# untitled.net
KiCad netlist of a schematic drawn in EAGLE
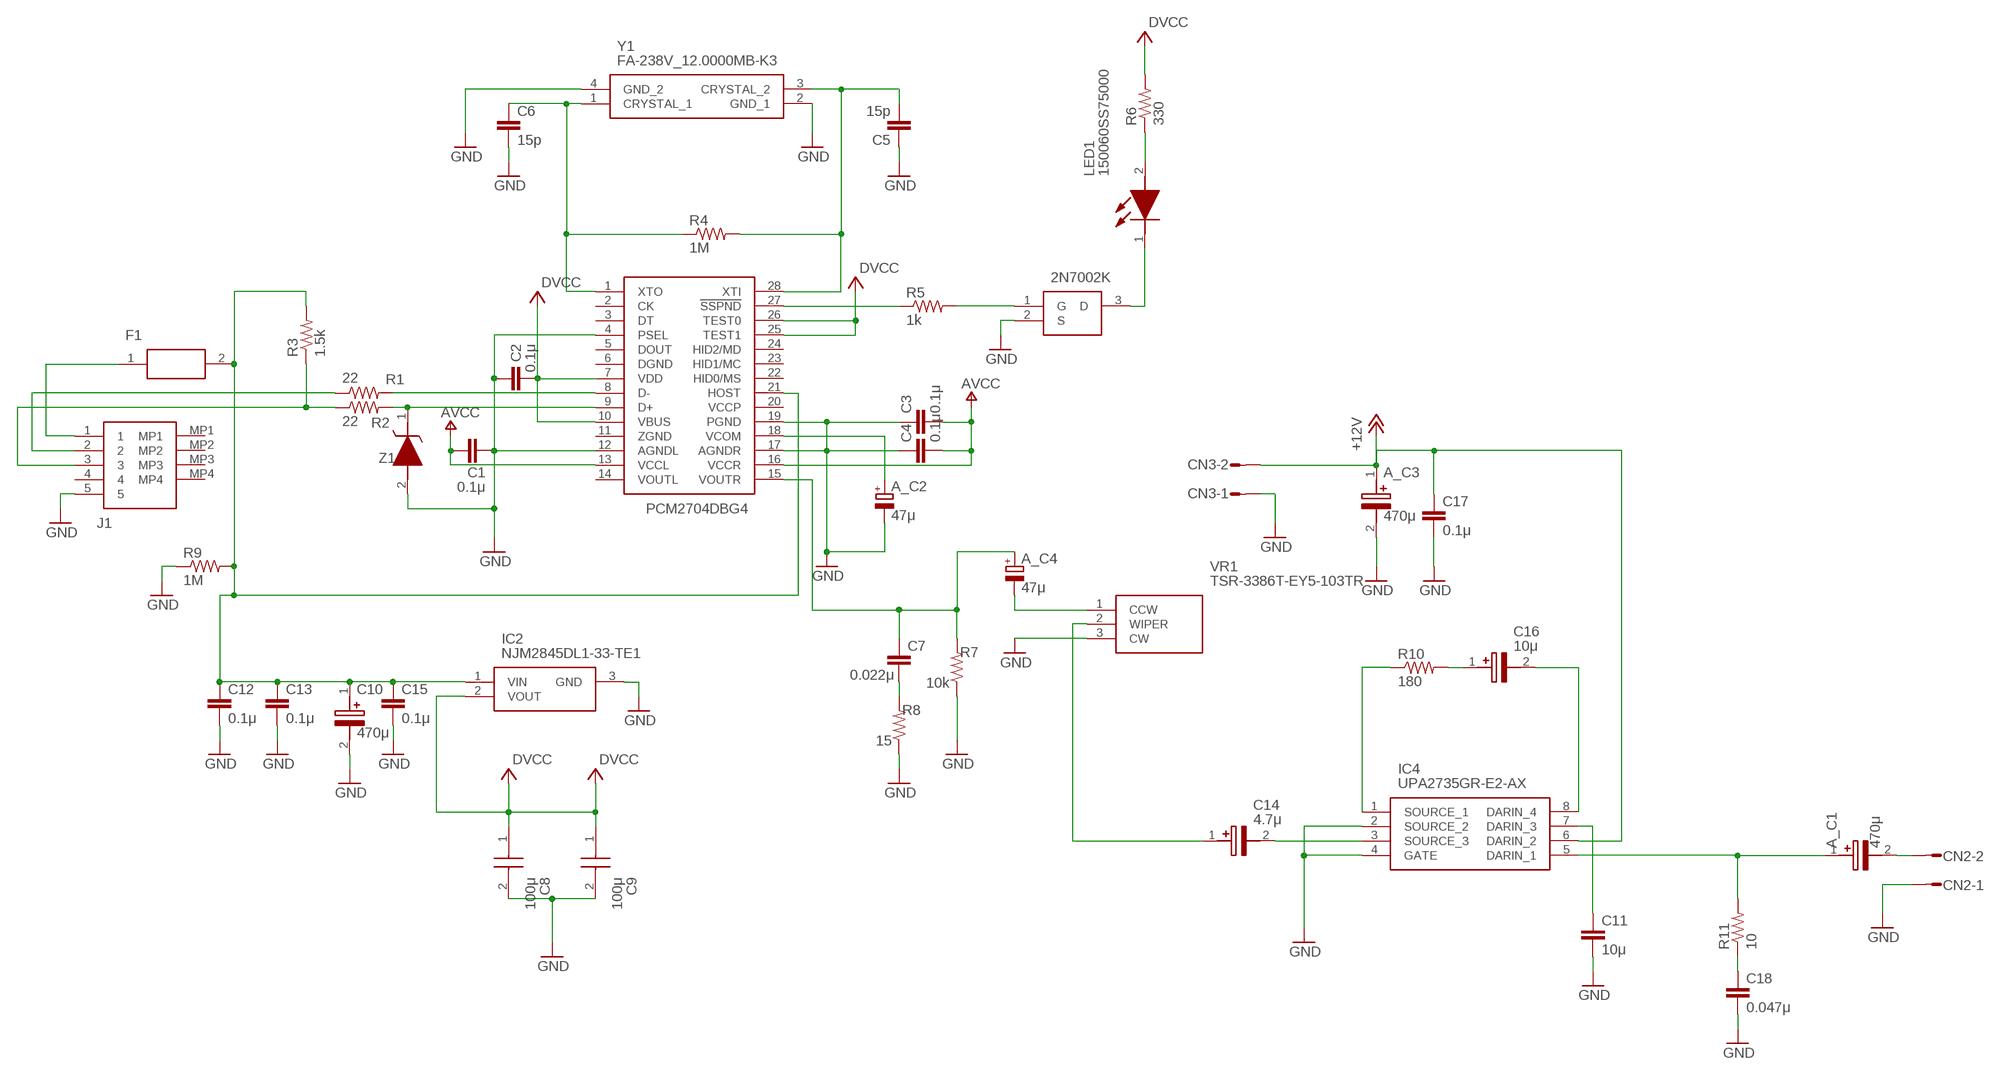
[diagram p0: schematic, sheet 1]

(export (version "E")
  (design (tool "Eeschema 10.0.6"))
  (components
    (comp (ref "A_C1")
      (value "470μ")
      (footprint "eagle-import:CAPPRD350W60D825H1150")
      (fields
        (field (name "MANUFACTURER_PART_NUMBER") "25PK470MEFC8X11.5")
        (field (name "MOUSER_PART_NUMBER") "232-25PK470MEFC8X115")
      )
      (libsource (lib "eagle-import") (part "25PK470MEFC8X11.5"))
    )
    (comp (ref "A_C2")
      (value "47μ")
      (footprint "eagle-import:UFG1E470MEM")
      (libsource (lib "eagle-import") (part "UFG1E470MEM"))
    )
    (comp (ref "A_C3")
      (value "470μ")
      (footprint "eagle-import:CAPPRD350W60D825H1150")
      (fields
        (field (name "MANUFACTURER_PART_NUMBER") "25PK470MEFC8X11.5")
        (field (name "MOUSER_PART_NUMBER") "232-25PK470MEFC8X115")
      )
      (libsource (lib "eagle-import") (part "25PK470MEFC8X11.5"))
    )
    (comp (ref "A_C4")
      (value "47μ")
      (footprint "eagle-import:UFG1E470MEM")
      (libsource (lib "eagle-import") (part "UFG1E470MEM"))
    )
    (comp (ref "C1")
      (value "0.1μ")
      (footprint "eagle-import:C0603")
      (libsource (lib "eagle-import") (part "C-EUC0603"))
    )
    (comp (ref "C2")
      (value "0.1μ")
      (footprint "eagle-import:C0603")
      (libsource (lib "eagle-import") (part "C-EUC0603"))
    )
    (comp (ref "C3")
      (value "0.1μ")
      (footprint "eagle-import:C0603")
      (libsource (lib "eagle-import") (part "C-EUC0603"))
    )
    (comp (ref "C4")
      (value "0.1μ")
      (footprint "eagle-import:C0603")
      (libsource (lib "eagle-import") (part "C-EUC0603"))
    )
    (comp (ref "C5")
      (value "15p")
      (footprint "eagle-import:C0603")
      (libsource (lib "eagle-import") (part "C-EUC0603"))
    )
    (comp (ref "C6")
      (value "15p")
      (footprint "eagle-import:C0603")
      (libsource (lib "eagle-import") (part "C-EUC0603"))
    )
    (comp (ref "C7")
      (value "0.022μ")
      (footprint "eagle-import:C0603")
      (libsource (lib "eagle-import") (part "C-EUC0603"))
    )
    (comp (ref "C8")
      (value "100μ")
      (footprint "eagle-import:PK(5X11)")
      (fields
        (field (name "MANUFACTURER_PART_NUMBER") "25PK100MEFC5X11")
        (field (name "MOUSER_PART_NUMBER") "232-25PK100MEFC5X11")
      )
      (libsource (lib "eagle-import") (part "25PK100MEFC5X11"))
    )
    (comp (ref "C9")
      (value "100μ")
      (footprint "eagle-import:PK(5X11)")
      (fields
        (field (name "MANUFACTURER_PART_NUMBER") "25PK100MEFC5X11")
        (field (name "MOUSER_PART_NUMBER") "232-25PK100MEFC5X11")
      )
      (libsource (lib "eagle-import") (part "25PK100MEFC5X11"))
    )
    (comp (ref "C10")
      (value "470μ")
      (footprint "eagle-import:CAPPRD350W60D825H1150")
      (fields
        (field (name "MANUFACTURER_PART_NUMBER") "25PK470MEFC8X11.5")
        (field (name "MOUSER_PART_NUMBER") "232-25PK470MEFC8X115")
      )
      (libsource (lib "eagle-import") (part "25PK470MEFC8X11.5"))
    )
    (comp (ref "C11")
      (value "10μ")
      (footprint "eagle-import:50F2D473J")
      (libsource (lib "eagle-import") (part "50F2D473J"))
    )
    (comp (ref "C12")
      (value "0.1μ")
      (footprint "eagle-import:C0603")
      (libsource (lib "eagle-import") (part "C-EUC0603"))
    )
    (comp (ref "C13")
      (value "0.1μ")
      (footprint "eagle-import:C0603")
      (libsource (lib "eagle-import") (part "C-EUC0603"))
    )
    (comp (ref "C14")
      (value "4.7μ")
      (footprint "eagle-import:CAPPRD200W50D525H1100")
      (fields (field (name "MANUFACTURER_PART_NUMBER") "50PK4R7MEFC5X11"))
      (libsource (lib "eagle-import") (part "50PK4R7MEFC5X11"))
    )
    (comp (ref "C15")
      (value "0.1μ")
      (footprint "eagle-import:C0603")
      (libsource (lib "eagle-import") (part "C-EUC0603"))
    )
    (comp (ref "C16")
      (value "10μ")
      (footprint "eagle-import:CAPPRD200W50D550H1250")
      (fields
        (field (name "MANUFACTURER_PART_NUMBER") "50PK10MEFC5X11")
        (field (name "MOUSER_PART_NUMBER") "232-50PK10MEFC5X11")
      )
      (libsource (lib "eagle-import") (part "50PK10MEFC5X11"))
    )
    (comp (ref "C17")
      (value "0.1μ")
      (footprint "eagle-import:C0603")
      (libsource (lib "eagle-import") (part "C-EUC0603"))
    )
    (comp (ref "C18")
      (value "0.047μ")
      (footprint "eagle-import:50F2D473J")
      (libsource (lib "eagle-import") (part "50F2D473J"))
    )
    (comp (ref "CN2")
      (value "S02P")
      (footprint "eagle-import:S02P")
      (libsource (lib "eagle-import") (part "S02P"))
    )
    (comp (ref "CN3")
      (value "S02P")
      (footprint "eagle-import:S02P")
      (libsource (lib "eagle-import") (part "S02P"))
    )
    (comp (ref "F1")
      (value "MICROSMD010-2")
      (footprint "eagle-import:MICROSMD175F2")
      (libsource (lib "eagle-import") (part "MICROSMD010-2"))
    )
    (comp (ref "IC1")
      (value "PCM2704DBG4")
      (footprint "eagle-import:SOP65P780X200-28N")
      (fields (field (name "MOUSER_PART_NUMBER") "595-PCM2704DBG4"))
      (libsource (lib "eagle-import") (part "PCM2704DBG4"))
    )
    (comp (ref "IC2")
      (value "NJM2845DL1-33-TE1")
      (footprint "eagle-import:TO-252-3-L1")
      (fields (field (name "MOUSER_PART_NUMBER") "513-NJM2845DL133-TE1"))
      (libsource (lib "eagle-import") (part "NJM2845DL1-33-TE1"))
    )
    (comp (ref "IC3")
      (value "2N7002K")
      (footprint "eagle-import:SOT65P210X110-3N")
      (fields
        (field (name "MANUFACTURER_PART_NUMBER") "2N7002KW")
        (field (name "MOUSER_PART_NUMBER") "512-2N7002KW")
      )
      (libsource (lib "eagle-import") (part "2N7002KW"))
    )
    (comp (ref "IC4")
      (value "UPA2735GR-E2-AX")
      (footprint "eagle-import:SOIC127P600X175-8N")
      (libsource (lib "eagle-import") (part "UPA2735GR-E2-AX"))
    )
    (comp (ref "J1")
      (value "USB2066-05-RBHM-15-STB-00-00-A")
      (footprint "eagle-import:USB206605RBHM15STB0000A")
      (fields (field (name "MOUSER_PART_NUMBER") "640-2665RBHM15STB00A"))
      (libsource (lib "eagle-import") (part "USB2066-05-RBHM-15-STB-00-00-A"))
    )
    (comp (ref "LED1")
      (value "150060SS75000")
      (footprint "eagle-import:LEDC1608X80N")
      (fields (field (name "MOUSER_PART_NUMBER") "710-150060SS75000"))
      (libsource (lib "eagle-import") (part "150060SS75000"))
    )
    (comp (ref "R1")
      (value "22")
      (footprint "eagle-import:R0603")
      (libsource (lib "eagle-import") (part "R-US_R0603"))
    )
    (comp (ref "R2")
      (value "22")
      (footprint "eagle-import:R0603")
      (libsource (lib "eagle-import") (part "R-US_R0603"))
    )
    (comp (ref "R3")
      (value "1.5k")
      (footprint "eagle-import:R0603")
      (libsource (lib "eagle-import") (part "R-US_R0603"))
    )
    (comp (ref "R4")
      (value "1M")
      (footprint "eagle-import:R0603")
      (libsource (lib "eagle-import") (part "R-US_R0603"))
    )
    (comp (ref "R5")
      (value "1k")
      (footprint "eagle-import:R0603")
      (libsource (lib "eagle-import") (part "R-US_R0603"))
    )
    (comp (ref "R6")
      (value "330")
      (footprint "eagle-import:R0603")
      (libsource (lib "eagle-import") (part "R-US_R0603"))
    )
    (comp (ref "R7")
      (value "10k")
      (footprint "eagle-import:R0603")
      (libsource (lib "eagle-import") (part "R-US_R0603"))
    )
    (comp (ref "R8")
      (value "15")
      (footprint "eagle-import:R0603")
      (libsource (lib "eagle-import") (part "R-US_R0603"))
    )
    (comp (ref "R9")
      (value "1M")
      (footprint "eagle-import:R0603")
      (libsource (lib "eagle-import") (part "R-US_R0603"))
    )
    (comp (ref "R10")
      (value "180")
      (footprint "eagle-import:R0603")
      (libsource (lib "eagle-import") (part "R-US_R0603"))
    )
    (comp (ref "R11")
      (value "10")
      (footprint "eagle-import:R0603")
      (libsource (lib "eagle-import") (part "R-US_R0603"))
    )
    (comp (ref "VR1")
      (value "TSR-3386T-EY5-103TR")
      (footprint "eagle-import:TSR3386TEY5103TR")
      (libsource (lib "eagle-import") (part "TSR-3386T-EY5-103TR"))
    )
    (comp (ref "Y1")
      (value "FA-238V_12.0000MB-K3")
      (footprint "eagle-import:FA238V120000MBK3")
      (fields
        (field (name "MANUFACTURER_PART_NUMBER") "FA-238V 12.0000MB-K3")
        (field (name "MOUSER_PART_NUMBER") "732-FA238V12.B-K3")
      )
      (libsource (lib "eagle-import") (part "FA-238V_12.0000MB-K3"))
    )
    (comp (ref "Z1")
      (value "UDZVTE-175.1B")
      (footprint "eagle-import:UDZVTE1751B")
      (fields (field (name "MOUSER_PART_NUMBER") "755-UDZVTE-175.1B"))
      (libsource (lib "eagle-import") (part "UDZVTE-175.1B"))
    )
  )
  (nets
    (net (code "1") (name "+12V") (class "Default")
      (node (ref "A_C3") (pin "1") (pinfunction "+_1") (pintype "bidirectional"))
      (node (ref "C17") (pin "1") (pinfunction "1_1") (pintype "passive"))
      (node (ref "CN3") (pin "2") (pinfunction "S_2") (pintype "passive"))
      (node (ref "IC4") (pin "6") (pinfunction "DARIN_2_6") (pintype "bidirectional"))
    )
    (net (code "2") (name "AVCC") (class "Default")
      (node (ref "C1") (pin "1") (pinfunction "1_1") (pintype "passive"))
      (node (ref "C3") (pin "2") (pinfunction "2_2") (pintype "passive"))
      (node (ref "C4") (pin "2") (pinfunction "2_2") (pintype "passive"))
      (node (ref "IC1") (pin "13") (pinfunction "VCCL_13") (pintype "bidirectional"))
      (node (ref "IC1") (pin "16") (pinfunction "VCCR_16") (pintype "bidirectional"))
    )
    (net (code "3") (name "DVCC") (class "Default")
      (node (ref "C2") (pin "2") (pinfunction "2_2") (pintype "passive"))
      (node (ref "C8") (pin "1") (pinfunction "-_1") (pintype "bidirectional"))
      (node (ref "C9") (pin "1") (pinfunction "-_1") (pintype "bidirectional"))
      (node (ref "IC1") (pin "10") (pinfunction "VBUS_10") (pintype "bidirectional"))
      (node (ref "IC1") (pin "25") (pinfunction "TEST1_25") (pintype "bidirectional"))
      (node (ref "IC1") (pin "26") (pinfunction "TEST0_26") (pintype "bidirectional"))
      (node (ref "IC1") (pin "7") (pinfunction "VDD_7") (pintype "bidirectional"))
      (node (ref "IC2") (pin "2") (pinfunction "VOUT_2") (pintype "bidirectional"))
      (node (ref "R6") (pin "2") (pinfunction "2_2") (pintype "passive"))
    )
    (net (code "4") (name "GND") (class "Default")
      (node (ref "A_C2") (pin "P$2") (pinfunction "-_P$2") (pintype "passive"))
      (node (ref "A_C3") (pin "2") (pinfunction "-_2") (pintype "bidirectional"))
      (node (ref "C1") (pin "2") (pinfunction "2_2") (pintype "passive"))
      (node (ref "C10") (pin "2") (pinfunction "-_2") (pintype "bidirectional"))
      (node (ref "C11") (pin "P$2") (pinfunction "2_P$2") (pintype "passive"))
      (node (ref "C12") (pin "2") (pinfunction "2_2") (pintype "passive"))
      (node (ref "C13") (pin "2") (pinfunction "2_2") (pintype "passive"))
      (node (ref "C15") (pin "2") (pinfunction "2_2") (pintype "passive"))
      (node (ref "C17") (pin "2") (pinfunction "2_2") (pintype "passive"))
      (node (ref "C18") (pin "P$2") (pinfunction "2_P$2") (pintype "passive"))
      (node (ref "C2") (pin "1") (pinfunction "1_1") (pintype "passive"))
      (node (ref "C3") (pin "1") (pinfunction "1_1") (pintype "passive"))
      (node (ref "C4") (pin "1") (pinfunction "1_1") (pintype "passive"))
      (node (ref "C5") (pin "1") (pinfunction "1_1") (pintype "passive"))
      (node (ref "C6") (pin "2") (pinfunction "2_2") (pintype "passive"))
      (node (ref "C8") (pin "2") (pinfunction "+_2") (pintype "bidirectional"))
      (node (ref "C9") (pin "2") (pinfunction "+_2") (pintype "bidirectional"))
      (node (ref "CN2") (pin "1") (pinfunction "S_1") (pintype "passive"))
      (node (ref "CN3") (pin "1") (pinfunction "S_1") (pintype "passive"))
      (node (ref "IC1") (pin "12") (pinfunction "AGNDL_12") (pintype "bidirectional"))
      (node (ref "IC1") (pin "17") (pinfunction "AGNDR_17") (pintype "bidirectional"))
      (node (ref "IC1") (pin "19") (pinfunction "PGND_19") (pintype "bidirectional"))
      (node (ref "IC1") (pin "4") (pinfunction "PSEL_4") (pintype "bidirectional"))
      (node (ref "IC2") (pin "3") (pinfunction "GND_3") (pintype "bidirectional"))
      (node (ref "IC3") (pin "2") (pinfunction "S_2") (pintype "bidirectional"))
      (node (ref "IC4") (pin "2") (pinfunction "SOURCE_2_2") (pintype "bidirectional"))
      (node (ref "IC4") (pin "4") (pinfunction "GATE_4") (pintype "bidirectional"))
      (node (ref "J1") (pin "5") (pinfunction "5_5") (pintype "bidirectional"))
      (node (ref "R7") (pin "1") (pinfunction "1_1") (pintype "passive"))
      (node (ref "R8") (pin "1") (pinfunction "1_1") (pintype "passive"))
      (node (ref "R9") (pin "1") (pinfunction "1_1") (pintype "passive"))
      (node (ref "VR1") (pin "3") (pinfunction "CW_3") (pintype "bidirectional"))
      (node (ref "Y1") (pin "2") (pinfunction "GND_1_2") (pintype "bidirectional"))
      (node (ref "Y1") (pin "4") (pinfunction "GND_2_4") (pintype "bidirectional"))
      (node (ref "Z1") (pin "2") (pinfunction "A_2") (pintype "bidirectional"))
    )
    (net (code "5") (name "Net-(A_C1-+)") (class "Default")
      (node (ref "A_C1") (pin "1") (pinfunction "+_1") (pintype "bidirectional"))
      (node (ref "IC4") (pin "5") (pinfunction "DARIN_1_5") (pintype "bidirectional"))
      (node (ref "R11") (pin "2") (pinfunction "2_2") (pintype "passive"))
    )
    (net (code "6") (name "Net-(A_C1--)") (class "Default")
      (node (ref "A_C1") (pin "2") (pinfunction "-_2") (pintype "bidirectional"))
      (node (ref "CN2") (pin "2") (pinfunction "S_2") (pintype "passive"))
    )
    (net (code "7") (name "Net-(A_C2-+)") (class "Default")
      (node (ref "A_C2") (pin "P$1") (pinfunction "+_P$1") (pintype "passive"))
      (node (ref "IC1") (pin "18") (pinfunction "VCOM_18") (pintype "bidirectional"))
    )
    (net (code "8") (name "Net-(A_C4-+)") (class "Default")
      (node (ref "A_C4") (pin "P$1") (pinfunction "+_P$1") (pintype "passive"))
      (node (ref "C7") (pin "1") (pinfunction "1_1") (pintype "passive"))
      (node (ref "IC1") (pin "15") (pinfunction "VOUTR_15") (pintype "bidirectional"))
      (node (ref "R7") (pin "2") (pinfunction "2_2") (pintype "passive"))
    )
    (net (code "9") (name "Net-(A_C4--)") (class "Default")
      (node (ref "A_C4") (pin "P$2") (pinfunction "-_P$2") (pintype "passive"))
      (node (ref "VR1") (pin "1") (pinfunction "CCW_1") (pintype "bidirectional"))
    )
    (net (code "10") (name "Net-(C7-Pad2)") (class "Default")
      (node (ref "C7") (pin "2") (pinfunction "2_2") (pintype "passive"))
      (node (ref "R8") (pin "2") (pinfunction "2_2") (pintype "passive"))
    )
    (net (code "11") (name "Net-(C10-+)") (class "Default")
      (node (ref "C10") (pin "1") (pinfunction "+_1") (pintype "bidirectional"))
      (node (ref "C12") (pin "1") (pinfunction "1_1") (pintype "passive"))
      (node (ref "C13") (pin "1") (pinfunction "1_1") (pintype "passive"))
      (node (ref "C15") (pin "1") (pinfunction "1_1") (pintype "passive"))
      (node (ref "F1") (pin "2") (pinfunction "2_2") (pintype "bidirectional"))
      (node (ref "IC1") (pin "21") (pinfunction "HOST_21") (pintype "bidirectional"))
      (node (ref "IC2") (pin "1") (pinfunction "VIN_1") (pintype "bidirectional"))
      (node (ref "R3") (pin "2") (pinfunction "2_2") (pintype "passive"))
      (node (ref "R9") (pin "2") (pinfunction "2_2") (pintype "passive"))
    )
    (net (code "12") (name "Net-(C11-1)") (class "Default")
      (node (ref "C11") (pin "P$1") (pinfunction "1_P$1") (pintype "passive"))
      (node (ref "IC4") (pin "7") (pinfunction "DARIN_3_7") (pintype "bidirectional"))
    )
    (net (code "13") (name "Net-(C14-+)") (class "Default")
      (node (ref "C14") (pin "1") (pinfunction "+_1") (pintype "bidirectional"))
      (node (ref "VR1") (pin "2") (pinfunction "WIPER_2") (pintype "bidirectional"))
    )
    (net (code "14") (name "Net-(C14--)") (class "Default")
      (node (ref "C14") (pin "2") (pinfunction "-_2") (pintype "bidirectional"))
      (node (ref "IC4") (pin "3") (pinfunction "SOURCE_3_3") (pintype "bidirectional"))
    )
    (net (code "15") (name "Net-(C16-+)") (class "Default")
      (node (ref "C16") (pin "1") (pinfunction "+_1") (pintype "power_in"))
      (node (ref "R10") (pin "2") (pinfunction "2_2") (pintype "passive"))
    )
    (net (code "16") (name "Net-(C16--)") (class "Default")
      (node (ref "C16") (pin "2") (pinfunction "-_2") (pintype "power_in"))
      (node (ref "IC4") (pin "8") (pinfunction "DARIN_4_8") (pintype "bidirectional"))
    )
    (net (code "17") (name "Net-(C18-1)") (class "Default")
      (node (ref "C18") (pin "P$1") (pinfunction "1_P$1") (pintype "passive"))
      (node (ref "R11") (pin "1") (pinfunction "1_1") (pintype "passive"))
    )
    (net (code "18") (name "Net-(F1-Pad1)") (class "Default")
      (node (ref "F1") (pin "1") (pinfunction "1_1") (pintype "bidirectional"))
      (node (ref "J1") (pin "1") (pinfunction "1_1") (pintype "bidirectional"))
    )
    (net (code "19") (name "Net-(IC1-D+)") (class "Default")
      (node (ref "IC1") (pin "9") (pinfunction "D+_9") (pintype "bidirectional"))
      (node (ref "R2") (pin "2") (pinfunction "2_2") (pintype "passive"))
      (node (ref "Z1") (pin "1") (pinfunction "K_1") (pintype "bidirectional"))
    )
    (net (code "20") (name "Net-(IC1-D-)") (class "Default")
      (node (ref "IC1") (pin "8") (pinfunction "D-_8") (pintype "bidirectional"))
      (node (ref "R1") (pin "2") (pinfunction "2_2") (pintype "passive"))
    )
    (net (code "21") (name "Net-(IC1-XTI)") (class "Default")
      (node (ref "C5") (pin "2") (pinfunction "2_2") (pintype "passive"))
      (node (ref "IC1") (pin "28") (pinfunction "XTI_28") (pintype "bidirectional"))
      (node (ref "R4") (pin "2") (pinfunction "2_2") (pintype "passive"))
      (node (ref "Y1") (pin "3") (pinfunction "CRYSTAL_2_3") (pintype "bidirectional"))
    )
    (net (code "22") (name "Net-(IC1-XTO)") (class "Default")
      (node (ref "C6") (pin "1") (pinfunction "1_1") (pintype "passive"))
      (node (ref "IC1") (pin "1") (pinfunction "XTO_1") (pintype "bidirectional"))
      (node (ref "R4") (pin "1") (pinfunction "1_1") (pintype "passive"))
      (node (ref "Y1") (pin "1") (pinfunction "CRYSTAL_1_1") (pintype "bidirectional"))
    )
    (net (code "23") (name "Net-(IC1-~{SSPND})") (class "Default")
      (node (ref "IC1") (pin "27") (pinfunction "~{SSPND}_27") (pintype "bidirectional"))
      (node (ref "R5") (pin "1") (pinfunction "1_1") (pintype "passive"))
    )
    (net (code "24") (name "Net-(IC3-D)") (class "Default")
      (node (ref "IC3") (pin "3") (pinfunction "D_3") (pintype "bidirectional"))
      (node (ref "LED1") (pin "1") (pinfunction "K_1") (pintype "bidirectional"))
    )
    (net (code "25") (name "Net-(IC3-G)") (class "Default")
      (node (ref "IC3") (pin "1") (pinfunction "G_1") (pintype "bidirectional"))
      (node (ref "R5") (pin "2") (pinfunction "2_2") (pintype "passive"))
    )
    (net (code "26") (name "Net-(IC4-SOURCE_1)") (class "Default")
      (node (ref "IC4") (pin "1") (pinfunction "SOURCE_1_1") (pintype "bidirectional"))
      (node (ref "R10") (pin "1") (pinfunction "1_1") (pintype "passive"))
    )
    (net (code "27") (name "Net-(J1-Pad2)") (class "Default")
      (node (ref "J1") (pin "2") (pinfunction "2_2") (pintype "bidirectional"))
      (node (ref "R1") (pin "1") (pinfunction "1_1") (pintype "passive"))
    )
    (net (code "28") (name "Net-(J1-Pad3)") (class "Default")
      (node (ref "J1") (pin "3") (pinfunction "3_3") (pintype "bidirectional"))
      (node (ref "R2") (pin "1") (pinfunction "1_1") (pintype "passive"))
      (node (ref "R3") (pin "1") (pinfunction "1_1") (pintype "passive"))
    )
    (net (code "29") (name "Net-(LED1-A)") (class "Default")
      (node (ref "LED1") (pin "2") (pinfunction "A_2") (pintype "bidirectional"))
      (node (ref "R6") (pin "1") (pinfunction "1_1") (pintype "passive"))
    )
    (net (code "30") (name "unconnected-(IC1-CK-Pad2)") (class "Default")
      (node (ref "IC1") (pin "2") (pinfunction "CK_2") (pintype "bidirectional"))
    )
    (net (code "31") (name "unconnected-(IC1-DGND-Pad6)") (class "Default")
      (node (ref "IC1") (pin "6") (pinfunction "DGND_6") (pintype "bidirectional"))
    )
    (net (code "32") (name "unconnected-(IC1-DOUT-Pad5)") (class "Default")
      (node (ref "IC1") (pin "5") (pinfunction "DOUT_5") (pintype "bidirectional"))
    )
    (net (code "33") (name "unconnected-(IC1-DT-Pad3)") (class "Default")
      (node (ref "IC1") (pin "3") (pinfunction "DT_3") (pintype "bidirectional"))
    )
    (net (code "34") (name "unconnected-(IC1-HID0{slash}MS-Pad22)") (class "Default")
      (node (ref "IC1") (pin "22") (pinfunction "HID0/MS_22") (pintype "bidirectional"))
    )
    (net (code "35") (name "unconnected-(IC1-HID1{slash}MC-Pad23)") (class "Default")
      (node (ref "IC1") (pin "23") (pinfunction "HID1/MC_23") (pintype "bidirectional"))
    )
    (net (code "36") (name "unconnected-(IC1-HID2{slash}MD-Pad24)") (class "Default")
      (node (ref "IC1") (pin "24") (pinfunction "HID2/MD_24") (pintype "bidirectional"))
    )
    (net (code "37") (name "unconnected-(IC1-VCCP-Pad20)") (class "Default")
      (node (ref "IC1") (pin "20") (pinfunction "VCCP_20") (pintype "bidirectional"))
    )
    (net (code "38") (name "unconnected-(IC1-VOUTL-Pad14)") (class "Default")
      (node (ref "IC1") (pin "14") (pinfunction "VOUTL_14") (pintype "bidirectional"))
    )
    (net (code "39") (name "unconnected-(IC1-ZGND-Pad11)") (class "Default")
      (node (ref "IC1") (pin "11") (pinfunction "ZGND_11") (pintype "bidirectional"))
    )
    (net (code "40") (name "unconnected-(J1-Pad4)") (class "Default")
      (node (ref "J1") (pin "4") (pinfunction "4_4") (pintype "bidirectional"))
    )
    (net (code "41") (name "unconnected-(J1-PadMP1)") (class "Default")
      (node (ref "J1") (pin "MP1") (pinfunction "MP1_MP1") (pintype "bidirectional"))
    )
    (net (code "42") (name "unconnected-(J1-PadMP2)") (class "Default")
      (node (ref "J1") (pin "MP2") (pinfunction "MP2_MP2") (pintype "bidirectional"))
    )
    (net (code "43") (name "unconnected-(J1-PadMP3)") (class "Default")
      (node (ref "J1") (pin "MP3") (pinfunction "MP3_MP3") (pintype "bidirectional"))
    )
    (net (code "44") (name "unconnected-(J1-PadMP4)") (class "Default")
      (node (ref "J1") (pin "MP4") (pinfunction "MP4_MP4") (pintype "bidirectional"))
    )
  )
)
